# DIOT_template.net
KiCad netlist of a schematic drawn in Altium Designer
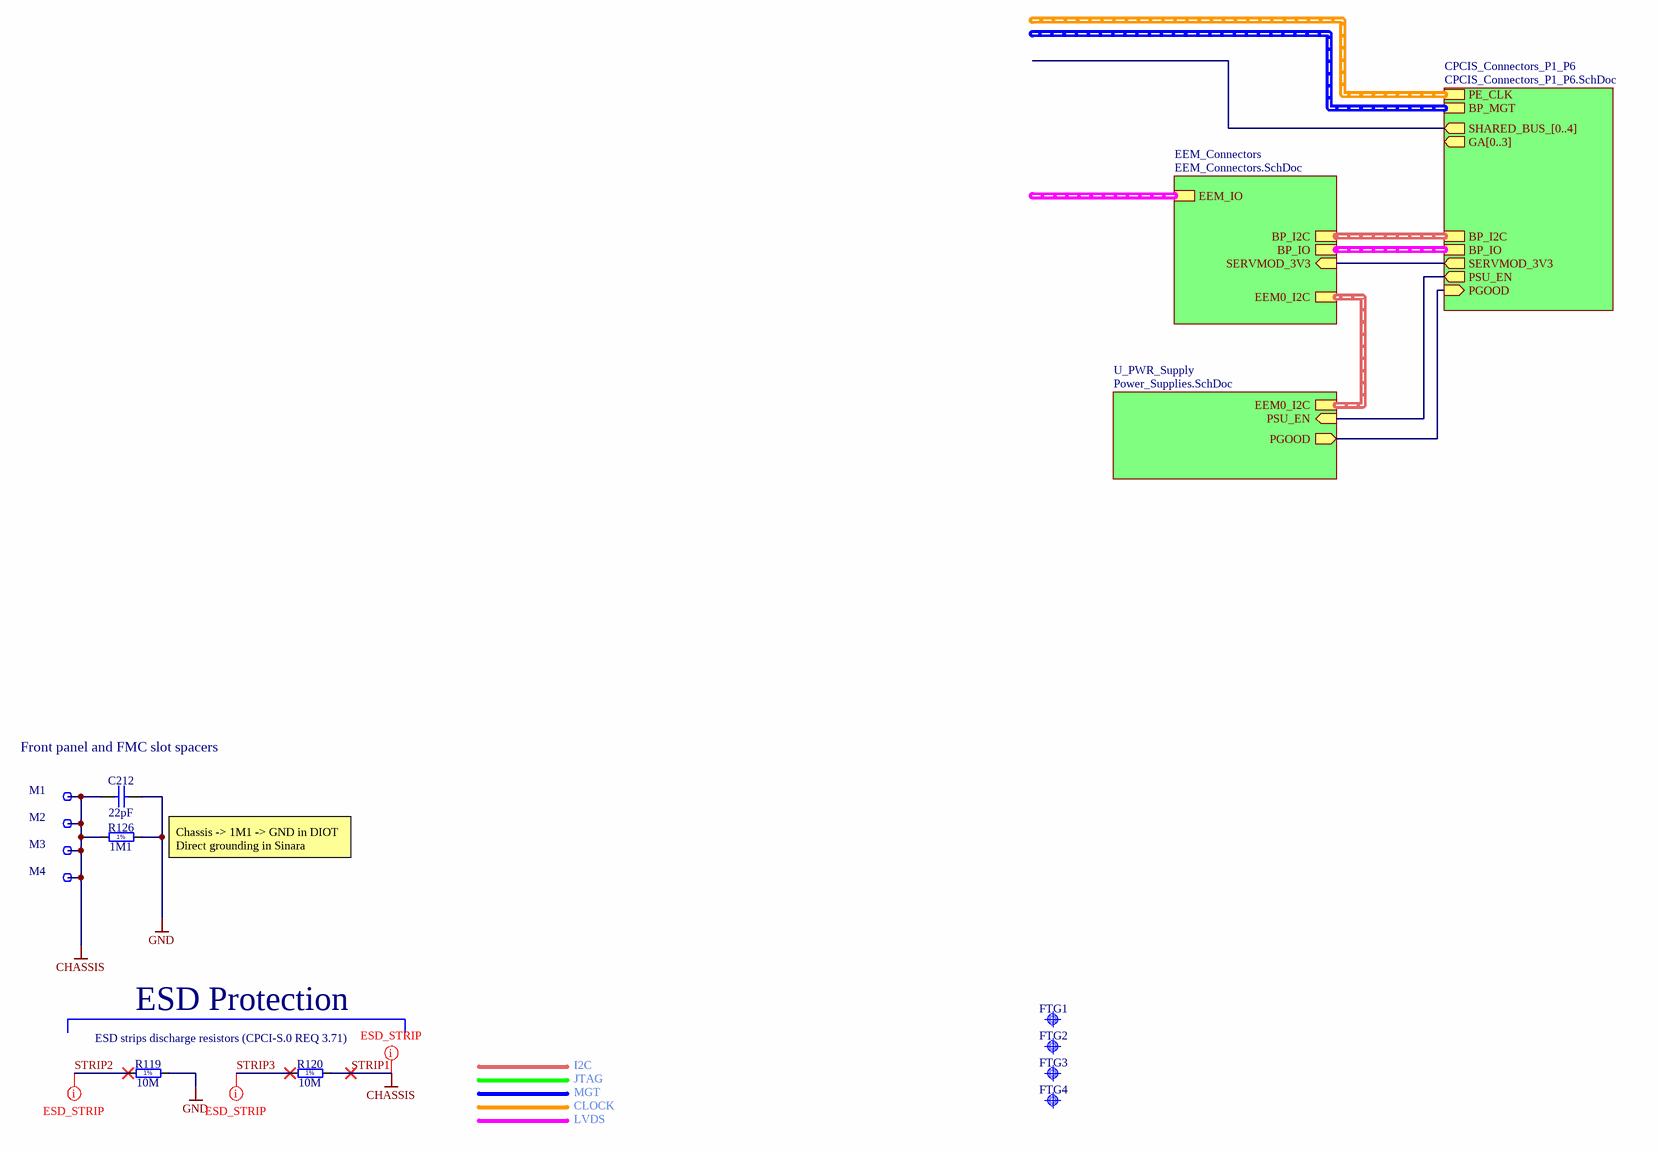
[diagram p0: DIOT_template.SchDoc]

(export (version "E")
  (design (tool "Eeschema 10.0.6"))
  (components
    (comp (ref "C212")
      (value "22pF")
      (footprint "CAPC1005X55N")
      (description "Non-polarised capacitor")
      (fields
        (field (name "PART NUMBER") "CC0402_22PF_50V_5%_C0G")
        (field (name "VOLTAGE") "50V")
        (field (name "AUTHOR") "CERN DEM JLC")
      )
      (libsource (lib "Capacitors") (part "Capacitor - non polarized"))
    )
    (comp (ref "FTG1")
      (value "Use only in PCB")
      (footprint "FIDUCIAL_TOP_C100-200")
      (description "Fiducial Target")
      (fields (field (name "PART NUMBER") "FIDUCIAL_TARGET_C100-200") (field (name "AUTHOR") "CERN DEM JLC"))
      (libsource (lib "Eletro-mechanical") (part "Fiducial Target"))
    )
    (comp (ref "FTG2")
      (value "Use only in PCB")
      (footprint "FIDUCIAL_TOP_S100-200")
      (description "Fiducial Target")
      (fields (field (name "PART NUMBER") "FIDUCIAL_TARGET_S100-200") (field (name "AUTHOR") "CERN DEM JLC"))
      (libsource (lib "Eletro-mechanical") (part "Fiducial Target"))
    )
    (comp (ref "FTG3")
      (value "Use only in PCB")
      (footprint "FIDUCIAL_TOP_S100-200")
      (description "Fiducial Target")
      (fields (field (name "PART NUMBER") "FIDUCIAL_TARGET_S100-200") (field (name "AUTHOR") "CERN DEM JLC"))
      (libsource (lib "Eletro-mechanical") (part "Fiducial Target"))
    )
    (comp (ref "FTG4")
      (value "Use only in PCB")
      (footprint "FIDUCIAL_TOP_S100-200")
      (description "Fiducial Target")
      (fields (field (name "PART NUMBER") "FIDUCIAL_TARGET_S100-200") (field (name "AUTHOR") "CERN DEM JLC"))
      (libsource (lib "Eletro-mechanical") (part "Fiducial Target"))
    )
    (comp (ref "M1")
      (value "Plated Hole")
      (footprint "MTG300_600")
      (description "Single Terminal Socket")
      (fields (field (name "PART NUMBER") "PLATED_HOLE3.0_PAD6.0") (field (name "AUTHOR") "CERN DEM JLC"))
      (libsource (lib "Eletro-mechanical") (part "Single Terminal Socket"))
    )
    (comp (ref "M2")
      (value "Plated Hole")
      (footprint "MTG300_600")
      (description "Single Terminal Socket")
      (fields (field (name "PART NUMBER") "PLATED_HOLE3.0_PAD6.0") (field (name "AUTHOR") "CERN DEM JLC"))
      (libsource (lib "Eletro-mechanical") (part "Single Terminal Socket"))
    )
    (comp (ref "M3")
      (value "Plated Hole")
      (footprint "MTG300_600")
      (description "Single Terminal Socket")
      (fields (field (name "PART NUMBER") "PLATED_HOLE3.0_PAD6.0") (field (name "AUTHOR") "CERN DEM JLC"))
      (libsource (lib "Eletro-mechanical") (part "Single Terminal Socket"))
    )
    (comp (ref "M4")
      (value "Plated Hole")
      (footprint "MTG300_600")
      (description "Single Terminal Socket")
      (fields (field (name "PART NUMBER") "PLATED_HOLE3.0_PAD6.0") (field (name "AUTHOR") "CERN DEM JLC"))
      (libsource (lib "Eletro-mechanical") (part "Single Terminal Socket"))
    )
    (comp (ref "R119")
      (value "10M")
      (footprint "RESC2113X55N")
      (description "Resistor - 1%")
      (fields
        (field (name "PART NUMBER") "R0805_10M_1%_0.125W_100PPM_VISHAY_CRCW e3")
        (field (name "POWER") "0.125W")
        (field (name "AUTHOR") "CERN DEM BC")
      )
      (libsource (lib "Resistors") (part "Resistor - 1%"))
    )
    (comp (ref "R120")
      (value "10M")
      (footprint "RESC2113X55N")
      (description "Resistor - 1%")
      (fields
        (field (name "PART NUMBER") "R0805_10M_1%_0.125W_100PPM_VISHAY_CRCW e3")
        (field (name "POWER") "0.125W")
        (field (name "AUTHOR") "CERN DEM BC")
      )
      (libsource (lib "Resistors") (part "Resistor - 1%"))
    )
    (comp (ref "R126")
      (value "1M1")
      (footprint "RESC2012X60N")
      (description "Resistor - 1%")
      (fields
        (field (name "PART NUMBER") "R0805_1M1_1%_0.125W_100PPM")
        (field (name "MANUFACTURER") "GENERIC")
        (field (name "AUTHOR") "CERN DEM JLC")
      )
      (libsource (lib "Resistors") (part "Resistor - 1%"))
    )
  )
  (nets
    (net (code "13") (name "/STRIP2") (class "Default")
      (node (ref "R119") (pin "1") (pinfunction "1_1") (pintype "passive+no_connect"))
    )
    (net (code "14") (name "/STRIP3") (class "Default")
      (node (ref "R120") (pin "1") (pinfunction "1_1") (pintype "passive+no_connect"))
    )
    (net (code "15") (name "CHASSIS") (class "Default")
      (node (ref "C212") (pin "1") (pinfunction "1_1") (pintype "passive"))
      (node (ref "M1") (pin "1") (pinfunction "1_1") (pintype "bidirectional"))
      (node (ref "M2") (pin "1") (pinfunction "1_1") (pintype "bidirectional"))
      (node (ref "M3") (pin "1") (pinfunction "1_1") (pintype "bidirectional"))
      (node (ref "M4") (pin "1") (pinfunction "1_1") (pintype "bidirectional"))
      (node (ref "R120") (pin "2") (pinfunction "2_2") (pintype "passive"))
      (node (ref "R126") (pin "1") (pinfunction "1_1") (pintype "passive"))
    )
    (net (code "16") (name "GND") (class "Default")
      (node (ref "C212") (pin "2") (pinfunction "2_2") (pintype "passive"))
      (node (ref "R119") (pin "2") (pinfunction "2_2") (pintype "passive"))
      (node (ref "R126") (pin "2") (pinfunction "2_2") (pintype "passive"))
    )
  )
)
